# Charger.net
KiCad netlist of a schematic drawn in Altium Designer
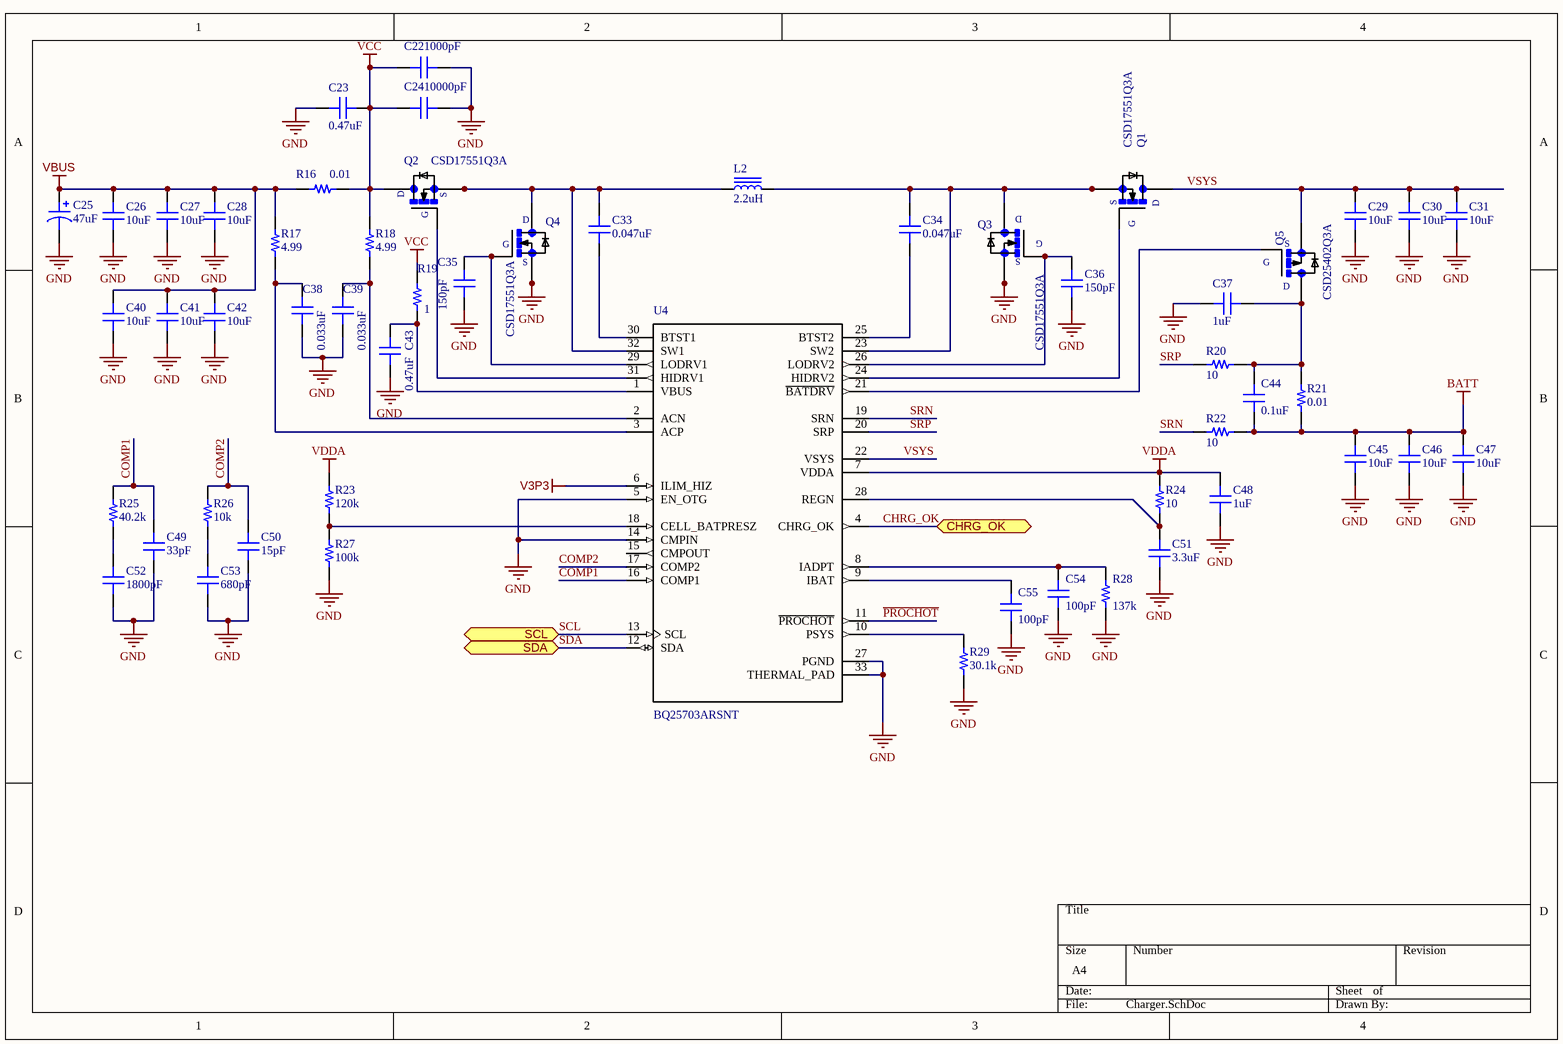
[diagram p0: Charger.SchDoc]

(export (version "E")
  (design (tool "Eeschema 10.0.6"))
  (components
    (comp (ref "C22")
      (value "1000pF")
      (footprint "CAP 0402/1005")
      (description "CAP CER 1000PF 50V X5R 0402")
      (fields
        (field (name "PART NUMBER") "GRM155R61H102KA01D")
        (field (name "MANUFACTURER") "Murata Electronics North America")
      )
      (libsource (lib "Celestial Library Database") (part "Capacitor"))
    )
    (comp (ref "C23")
      (value "0.47uF")
      (footprint "CAP 0603/1608")
      (description "CAP CER 0.47UF 50V X7R 0603")
      (fields
        (field (name "PART NUMBER") "C1608X7R1H474K080AC")
        (field (name "MANUFACTURER") "TDK Corporation")
      )
      (libsource (lib "Celestial Library Database") (part "Capacitor"))
    )
    (comp (ref "C24")
      (value "10000pF")
      (footprint "CAP 0402/1005")
      (description "CAP CER 10000PF 50V X7R 0402")
      (fields
        (field (name "PART NUMBER") "GCM155R71H103KA55D")
        (field (name "MANUFACTURER") "Murata Electronics North America")
      )
      (libsource (lib "Celestial Library Database") (part "Capacitor"))
    )
    (comp (ref "C25")
      (value "47uF")
      (footprint "CAP POL 2917/7343")
      (description "CAP TANT 47UF 35V 20% 2917")
      (fields (field (name "PART NUMBER") "T491X476M035AT") (field (name "MANUFACTURER") "Kemet"))
      (libsource (lib "Celestial Library Database") (part "Polarised Capacitor"))
    )
    (comp (ref "C26")
      (value "10uF")
      (footprint "CAP 0805/2012")
      (description "CAP CER 10UF 35V X5R 0805")
      (fields
        (field (name "PART NUMBER") "C2012X5R1V106M085AC")
        (field (name "MANUFACTURER") "TDK Corporation")
      )
      (libsource (lib "Celestial Library Database") (part "Capacitor"))
    )
    (comp (ref "C27")
      (value "10uF")
      (footprint "CAP 0805/2012")
      (description "CAP CER 10UF 35V X5R 0805")
      (fields
        (field (name "PART NUMBER") "C2012X5R1V106M085AC")
        (field (name "MANUFACTURER") "TDK Corporation")
      )
      (libsource (lib "Celestial Library Database") (part "Capacitor"))
    )
    (comp (ref "C28")
      (value "10uF")
      (footprint "CAP 0805/2012")
      (description "CAP CER 10UF 35V X5R 0805")
      (fields
        (field (name "PART NUMBER") "C2012X5R1V106M085AC")
        (field (name "MANUFACTURER") "TDK Corporation")
      )
      (libsource (lib "Celestial Library Database") (part "Capacitor"))
    )
    (comp (ref "C29")
      (value "10uF")
      (footprint "CAP 0805/2012")
      (description "CAP CER 10UF 35V X5R 0805")
      (fields
        (field (name "PART NUMBER") "C2012X5R1V106M085AC")
        (field (name "MANUFACTURER") "TDK Corporation")
      )
      (libsource (lib "Celestial Library Database") (part "Capacitor"))
    )
    (comp (ref "C30")
      (value "10uF")
      (footprint "CAP 0805/2012")
      (description "CAP CER 10UF 35V X5R 0805")
      (fields
        (field (name "PART NUMBER") "C2012X5R1V106M085AC")
        (field (name "MANUFACTURER") "TDK Corporation")
      )
      (libsource (lib "Celestial Library Database") (part "Capacitor"))
    )
    (comp (ref "C31")
      (value "10uF")
      (footprint "CAP 0805/2012")
      (description "CAP CER 10UF 35V X5R 0805")
      (fields
        (field (name "PART NUMBER") "C2012X5R1V106M085AC")
        (field (name "MANUFACTURER") "TDK Corporation")
      )
      (libsource (lib "Celestial Library Database") (part "Capacitor"))
    )
    (comp (ref "C33")
      (value "0.047uF")
      (footprint "CAP 0603/1608")
      (description "CAP CER 0.047UF 50V X7R 0603")
      (fields
        (field (name "PART NUMBER") "500R14W473KV4T")
        (field (name "MANUFACTURER") "Johanson Dielectrics Inc.")
      )
      (libsource (lib "Celestial Library Database") (part "Capacitor"))
    )
    (comp (ref "C34")
      (value "0.047uF")
      (footprint "CAP 0603/1608")
      (description "CAP CER 0.047UF 50V X7R 0603")
      (fields
        (field (name "PART NUMBER") "500R14W473KV4T")
        (field (name "MANUFACTURER") "Johanson Dielectrics Inc.")
      )
      (libsource (lib "Celestial Library Database") (part "Capacitor"))
    )
    (comp (ref "C35")
      (value "150pF")
      (footprint "CAP 0603/1608")
      (description "CAP CER 150PF 50V C0G 0603")
      (fields
        (field (name "PART NUMBER") "C1608C0G1H151K080AA")
        (field (name "MANUFACTURER") "TDK Corporation")
      )
      (libsource (lib "Celestial Library Database") (part "Capacitor"))
    )
    (comp (ref "C36")
      (value "150pF")
      (footprint "CAP 0603/1608")
      (description "CAP CER 150PF 50V C0G 0603")
      (fields
        (field (name "PART NUMBER") "C1608C0G1H151K080AA")
        (field (name "MANUFACTURER") "TDK Corporation")
      )
      (libsource (lib "Celestial Library Database") (part "Capacitor"))
    )
    (comp (ref "C37")
      (value "1uF")
      (footprint "CAP 0603/1608")
      (description "CAP CER 1UF 35V X7R 0603")
      (fields
        (field (name "PART NUMBER") "GRM188R7YA105KA12D")
        (field (name "MANUFACTURER") "Murata Electronics North America")
      )
      (libsource (lib "Celestial Library Database") (part "Capacitor"))
    )
    (comp (ref "C38")
      (value "0.033uF")
      (footprint "CAP 0603/1608")
      (description "CAP CER 0.033UF 50V X7R 0603")
      (fields
        (field (name "PART NUMBER") "C1608X7R1H333K080AA")
        (field (name "MANUFACTURER") "TDK Corporation")
      )
      (libsource (lib "Celestial Library Database") (part "Capacitor"))
    )
    (comp (ref "C39")
      (value "0.033uF")
      (footprint "CAP 0603/1608")
      (description "CAP CER 0.033UF 50V X7R 0603")
      (fields
        (field (name "PART NUMBER") "C1608X7R1H333K080AA")
        (field (name "MANUFACTURER") "TDK Corporation")
      )
      (libsource (lib "Celestial Library Database") (part "Capacitor"))
    )
    (comp (ref "C40")
      (value "10uF")
      (footprint "CAP 0805/2012")
      (description "CAP CER 10UF 35V X5R 0805")
      (fields
        (field (name "PART NUMBER") "C2012X5R1V106M085AC")
        (field (name "MANUFACTURER") "TDK Corporation")
      )
      (libsource (lib "Celestial Library Database") (part "Capacitor"))
    )
    (comp (ref "C41")
      (value "10uF")
      (footprint "CAP 0805/2012")
      (description "CAP CER 10UF 35V X5R 0805")
      (fields
        (field (name "PART NUMBER") "C2012X5R1V106M085AC")
        (field (name "MANUFACTURER") "TDK Corporation")
      )
      (libsource (lib "Celestial Library Database") (part "Capacitor"))
    )
    (comp (ref "C42")
      (value "10uF")
      (footprint "CAP 0805/2012")
      (description "CAP CER 10UF 35V X5R 0805")
      (fields
        (field (name "PART NUMBER") "C2012X5R1V106M085AC")
        (field (name "MANUFACTURER") "TDK Corporation")
      )
      (libsource (lib "Celestial Library Database") (part "Capacitor"))
    )
    (comp (ref "C43")
      (value "0.47uF")
      (footprint "CAP 0603/1608")
      (description "CAP CER 0.47UF 50V X5R 0603")
      (fields (field (name "PART NUMBER") "UMK107ABJ474KA-T") (field (name "MANUFACTURER") "Taiyo Yuden"))
      (libsource (lib "Celestial Library Database") (part "Capacitor"))
    )
    (comp (ref "C44")
      (value "0.1uF")
      (footprint "CAP 0603/1608")
      (description "CAP CER 0.1UF 25V X7R 0603")
      (fields
        (field (name "PART NUMBER") "C1608X7R1E104K080AA")
        (field (name "MANUFACTURER") "TDK Corporation")
      )
      (libsource (lib "Celestial Library Database") (part "Capacitor"))
    )
    (comp (ref "C45")
      (value "10uF")
      (footprint "CAP 0805/2012")
      (description "CAP CER 10UF 35V X5R 0805")
      (fields
        (field (name "PART NUMBER") "C2012X5R1V106M085AC")
        (field (name "MANUFACTURER") "TDK Corporation")
      )
      (libsource (lib "Celestial Library Database") (part "Capacitor"))
    )
    (comp (ref "C46")
      (value "10uF")
      (footprint "CAP 0805/2012")
      (description "CAP CER 10UF 35V X5R 0805")
      (fields
        (field (name "PART NUMBER") "C2012X5R1V106M085AC")
        (field (name "MANUFACTURER") "TDK Corporation")
      )
      (libsource (lib "Celestial Library Database") (part "Capacitor"))
    )
    (comp (ref "C47")
      (value "10uF")
      (footprint "CAP 0805/2012")
      (description "CAP CER 10UF 35V X5R 0805")
      (fields
        (field (name "PART NUMBER") "C2012X5R1V106M085AC")
        (field (name "MANUFACTURER") "TDK Corporation")
      )
      (libsource (lib "Celestial Library Database") (part "Capacitor"))
    )
    (comp (ref "C48")
      (value "1uF")
      (footprint "CAP 0603/1608")
      (description "CAP CER 1UF 35V X7R 0603")
      (fields
        (field (name "PART NUMBER") "GRM188R7YA105KA12D")
        (field (name "MANUFACTURER") "Murata Electronics North America")
      )
      (libsource (lib "Celestial Library Database") (part "Capacitor"))
    )
    (comp (ref "C49")
      (value "33pF")
      (footprint "CAP 0603/1608")
      (description "CAP CER 33PF 50V NPO 0603")
      (fields (field (name "PART NUMBER") "CC0603JRNPO9BN330") (field (name "MANUFACTURER") "Yageo"))
      (libsource (lib "Celestial Library Database") (part "Capacitor"))
    )
    (comp (ref "C50")
      (value "15pF")
      (footprint "CAP 0603/1608")
      (description "CAP CER 15PF 50V C0G/NP0 0603")
      (fields
        (field (name "PART NUMBER") "500R14N150JV4T")
        (field (name "MANUFACTURER") "Johanson Dielectrics Inc.")
      )
      (libsource (lib "Celestial Library Database") (part "Capacitor"))
    )
    (comp (ref "C51")
      (value "3.3uF")
      (footprint "CAP 0603/1608")
      (description "CAP CER 3.3UF 16V X5R 0603")
      (fields
        (field (name "PART NUMBER") "C1608X5R1C335K080AC")
        (field (name "MANUFACTURER") "TDK Corporation")
      )
      (libsource (lib "Celestial Library Database") (part "Capacitor"))
    )
    (comp (ref "C52")
      (value "1800pF")
      (footprint "CAP 0603/1608")
      (description "CAP CER 1800PF 50V X7R 0603")
      (fields
        (field (name "PART NUMBER") "CL10B182KB8NNNC")
        (field (name "MANUFACTURER") "Samsung Electro-Mechanics America, Inc.")
      )
      (libsource (lib "Celestial Library Database") (part "Capacitor"))
    )
    (comp (ref "C53")
      (value "680pF")
      (footprint "CAP 0603/1608")
      (description "CAP CER 680PF 50V X7R 0603")
      (fields
        (field (name "PART NUMBER") "CL10B681KB8NNNC")
        (field (name "MANUFACTURER") "Samsung Electro-Mechanics America, Inc.")
      )
      (libsource (lib "Celestial Library Database") (part "Capacitor"))
    )
    (comp (ref "C54")
      (value "100pF")
      (footprint "CAP 0603/1608")
      (description "CAP CER 100PF 50V NP0 0603")
      (fields
        (field (name "PART NUMBER") "CL10C101KB8NNNC")
        (field (name "MANUFACTURER") "Samsung Electro-Mechanics America, Inc.")
      )
      (libsource (lib "Celestial Library Database") (part "Capacitor"))
    )
    (comp (ref "C55")
      (value "100pF")
      (footprint "CAP 0603/1608")
      (description "CAP CER 100PF 50V NP0 0603")
      (fields
        (field (name "PART NUMBER") "CL10C101KB8NNNC")
        (field (name "MANUFACTURER") "Samsung Electro-Mechanics America, Inc.")
      )
      (libsource (lib "Celestial Library Database") (part "Capacitor"))
    )
    (comp (ref "L2")
      (value "2.2uH")
      (footprint "WURTH WE-HCI 7040")
      (description "FIXED IND 2.2UH 9A 11.4 MOHM SMD")
      (fields (field (name "PART NUMBER") "744311220") (field (name "MANUFACTURER") "Wurth Electronics Inc"))
      (libsource (lib "Celestial Library Database") (part "Inductor"))
    )
    (comp (ref "Q1")
      (value "CSD17551Q3A")
      (footprint "SON65P300X350X90-9N")
      (description "Trans MOSFET N-CH 30V 48A 8-Pin VSONP EP T/R")
      (fields (field (name "MF") "Texas Instruments"))
      (libsource (lib "CSD17551Q3A") (part "CSD17551Q3A"))
    )
    (comp (ref "Q2")
      (value "CSD17551Q3A")
      (footprint "SON65P300X350X90-9N")
      (description "Trans MOSFET N-CH 30V 48A 8-Pin VSONP EP T/R")
      (fields (field (name "MF") "Texas Instruments"))
      (libsource (lib "CSD17551Q3A") (part "CSD17551Q3A"))
    )
    (comp (ref "Q3")
      (value "CSD17551Q3A")
      (footprint "SON65P300X350X90-9N")
      (description "Trans MOSFET N-CH 30V 48A 8-Pin VSONP EP T/R")
      (fields (field (name "MF") "Texas Instruments"))
      (libsource (lib "CSD17551Q3A") (part "CSD17551Q3A"))
    )
    (comp (ref "Q4")
      (value "CSD17551Q3A")
      (footprint "SON65P300X350X90-9N")
      (description "Trans MOSFET N-CH 30V 48A 8-Pin VSONP EP T/R")
      (fields (field (name "MF") "Texas Instruments"))
      (libsource (lib "CSD17551Q3A") (part "CSD17551Q3A"))
    )
    (comp (ref "Q5")
      (value "CSD25402Q3A")
      (footprint "SON65P300X350X90-9N")
      (description "Trans MOSFET P-CH –20 V -15A NexFET™ Power MOSFET")
      (fields (field (name "MF") "Texas Instruments") (field (name "MP") "CSD17551Q3A"))
      (libsource (lib "CSD17551Q3A") (part "CSD25402Q3A"))
    )
    (comp (ref "R16")
      (value "0.01")
      (footprint "STACKPOLE CSR2512")
      (description "RES SMD 0.01 OHM 1% 1W 2512")
      (fields (field (name "PART NUMBER") "CSR25120R01F") (field (name "MANUFACTURER") "Riedon"))
      (libsource (lib "Celestial Library Database") (part "Resistor"))
    )
    (comp (ref "R17")
      (value "4.99")
      (footprint "RES 0603/1608")
      (description "RES SMD 4.99 OHM 1% 1/10W 0603")
      (fields (field (name "PART NUMBER") "RC0603FR-074R99L") (field (name "MANUFACTURER") "Yageo"))
      (libsource (lib "Celestial Library Database") (part "Resistor"))
    )
    (comp (ref "R18")
      (value "4.99")
      (footprint "RES 0603/1608")
      (description "RES SMD 4.99 OHM 1% 1/10W 0603")
      (fields (field (name "PART NUMBER") "RC0603FR-074R99L") (field (name "MANUFACTURER") "Yageo"))
      (libsource (lib "Celestial Library Database") (part "Resistor"))
    )
    (comp (ref "R19")
      (value "1")
      (footprint "RES 0603/1608")
      (description "RES SMD 1 OHM 5% 1/4W 0603")
      (fields (field (name "PART NUMBER") "RCS06031R00JNEA") (field (name "MANUFACTURER") "Vishay Dale"))
      (libsource (lib "Celestial Library Database") (part "Resistor"))
    )
    (comp (ref "R20")
      (value "10")
      (footprint "RES 0402/1005")
      (description "RES SMD 10 OHM 1% 1/10W 0402")
      (fields
        (field (name "PART NUMBER") "ERJ-2RKF10R0X")
        (field (name "MANUFACTURER") "Panasonic Electronic Components")
      )
      (libsource (lib "Celestial Library Database") (part "Resistor"))
    )
    (comp (ref "R21")
      (value "0.01")
      (footprint "STACKPOLE CSR2512")
      (description "RES SMD 0.01 OHM 1% 1W 2512")
      (fields (field (name "PART NUMBER") "CSR25120R01F") (field (name "MANUFACTURER") "Riedon"))
      (libsource (lib "Celestial Library Database") (part "Resistor"))
    )
    (comp (ref "R22")
      (value "10")
      (footprint "RES 0402/1005")
      (description "RES SMD 10 OHM 1% 1/10W 0402")
      (fields
        (field (name "PART NUMBER") "ERJ-2RKF10R0X")
        (field (name "MANUFACTURER") "Panasonic Electronic Components")
      )
      (libsource (lib "Celestial Library Database") (part "Resistor"))
    )
    (comp (ref "R23")
      (value "120k")
      (footprint "RES 0603/1608")
      (description "RES SMD 120K OHM 1% 1/10W 0603")
      (fields
        (field (name "PART NUMBER") "ERJ-3EKF1203V")
        (field (name "MANUFACTURER") "Panasonic Electronic Components")
      )
      (libsource (lib "Celestial Library Database") (part "Resistor"))
    )
    (comp (ref "R24")
      (value "10")
      (footprint "RES 0603/1608")
      (description "RES SMD 10 OHM 1% 1/10W 0603")
      (fields
        (field (name "PART NUMBER") "RMCF0603FT10R0")
        (field (name "MANUFACTURER") "Stackpole Electronics Inc.")
      )
      (libsource (lib "Celestial Library Database") (part "Resistor"))
    )
    (comp (ref "R25")
      (value "40.2k")
      (footprint "RES 0603/1608")
      (description "RES SMD 40.2K OHM 1% 1/10W 0603")
      (fields
        (field (name "PART NUMBER") "ERJ-3EKF4022V")
        (field (name "MANUFACTURER") "Panasonic Electronic Components")
      )
      (libsource (lib "Celestial Library Database") (part "Resistor"))
    )
    (comp (ref "R26")
      (value "10k")
      (footprint "RES 0603/1608")
      (description "RES SMD 10K OHM 1% 1/10W 0603")
      (fields
        (field (name "PART NUMBER") "ERJ-3EKF1002V")
        (field (name "MANUFACTURER") "Panasonic Electronic Components")
      )
      (libsource (lib "Celestial Library Database") (part "Resistor"))
    )
    (comp (ref "R27")
      (value "100k")
      (footprint "RES 0603/1608")
      (description "RES SMD 100K OHM 1% 1/10W 0603")
      (fields
        (field (name "PART NUMBER") "ERJ-3EKF1003V")
        (field (name "MANUFACTURER") "Panasonic Electronic Components")
      )
      (libsource (lib "Celestial Library Database") (part "Resistor"))
    )
    (comp (ref "R28")
      (value "137k")
      (footprint "RES 0603/1608")
      (description "RES SMD 137K OHM 1% 1/10W 0603")
      (fields
        (field (name "PART NUMBER") "ERJ-3EKF1373V")
        (field (name "MANUFACTURER") "Panasonic Electronic Components")
      )
      (libsource (lib "Celestial Library Database") (part "Resistor"))
    )
    (comp (ref "R29")
      (value "30.1k")
      (footprint "RES 0402/1005")
      (description "RES SMD 30.1K OHM 1% 1/10W 0402")
      (fields
        (field (name "PART NUMBER") "ERJ-2RKF3012X")
        (field (name "MANUFACTURER") "Panasonic Electronic Components")
      )
      (libsource (lib "Celestial Library Database") (part "Resistor"))
    )
    (comp (ref "U4")
      (value "BQ25703ARSNT")
      (footprint "QFN40P400X400X80-33N")
      (fields (field (name "MF") "Texas Instruments"))
      (libsource (lib "BQ25703ARSNT") (part "BQ25703ARSNT"))
    )
  )
  (nets
    (net (code "1") (name "/CHRG_OK") (class "Default")
      (node (ref "U4") (pin "4") (pinfunction "CHRG_OK_4") (pintype "output"))
    )
    (net (code "2") (name "/COMP1") (class "Default")
      (node (ref "C49") (pin "2") (pinfunction "2_2") (pintype "passive"))
      (node (ref "R25") (pin "2") (pinfunction "2_2") (pintype "passive"))
      (node (ref "U4") (pin "16") (pinfunction "COMP1_16") (pintype "input"))
    )
    (net (code "3") (name "/COMP2") (class "Default")
      (node (ref "C50") (pin "2") (pinfunction "2_2") (pintype "passive"))
      (node (ref "R26") (pin "2") (pinfunction "2_2") (pintype "passive"))
      (node (ref "U4") (pin "17") (pinfunction "COMP2_17") (pintype "input"))
    )
    (net (code "4") (name "/SCL") (class "Default")
      (node (ref "U4") (pin "13") (pinfunction "SCL_13") (pintype "input"))
    )
    (net (code "5") (name "/SDA") (class "Default")
      (node (ref "U4") (pin "12") (pinfunction "SDA_12") (pintype "bidirectional"))
    )
    (net (code "6") (name "/SRN") (class "Default")
      (node (ref "R22") (pin "1") (pinfunction "1_1") (pintype "passive"))
      (node (ref "U4") (pin "19") (pinfunction "SRN_19") (pintype "power_in"))
    )
    (net (code "7") (name "/SRP") (class "Default")
      (node (ref "R20") (pin "1") (pinfunction "1_1") (pintype "passive"))
      (node (ref "U4") (pin "20") (pinfunction "SRP_20") (pintype "power_in"))
    )
    (net (code "8") (name "/VSYS") (class "Default")
      (node (ref "C29") (pin "2") (pinfunction "2_2") (pintype "passive"))
      (node (ref "C30") (pin "2") (pinfunction "2_2") (pintype "passive"))
      (node (ref "C31") (pin "2") (pinfunction "2_2") (pintype "passive"))
      (node (ref "Q1") (pin "5") (pinfunction "D_5") (pintype "passive"))
      (node (ref "Q5") (pin "5") (pinfunction "D_5") (pintype "passive"))
      (node (ref "U4") (pin "22") (pinfunction "VSYS_22") (pintype "power_in"))
    )
    (net (code "9") (name "/~{PROCHOT}") (class "Default")
      (node (ref "U4") (pin "11") (pinfunction "~{PROCHOT}_11") (pintype "output"))
    )
    (net (code "10") (name "BATT") (class "Default")
      (node (ref "C44") (pin "1") (pinfunction "1_1") (pintype "passive"))
      (node (ref "C45") (pin "1") (pinfunction "1_1") (pintype "passive"))
      (node (ref "C46") (pin "2") (pinfunction "2_2") (pintype "passive"))
      (node (ref "C47") (pin "2") (pinfunction "2_2") (pintype "passive"))
      (node (ref "R21") (pin "1") (pinfunction "1_1") (pintype "passive"))
      (node (ref "R22") (pin "2") (pinfunction "2_2") (pintype "passive"))
    )
    (net (code "11") (name "GND") (class "Default")
      (node (ref "C22") (pin "2") (pinfunction "2_2") (pintype "passive"))
      (node (ref "C23") (pin "2") (pinfunction "2_2") (pintype "passive"))
      (node (ref "C24") (pin "2") (pinfunction "2_2") (pintype "passive"))
      (node (ref "C25") (pin "2") (pinfunction "2_2") (pintype "passive"))
      (node (ref "C26") (pin "1") (pinfunction "1_1") (pintype "passive"))
      (node (ref "C27") (pin "1") (pinfunction "1_1") (pintype "passive"))
      (node (ref "C28") (pin "1") (pinfunction "1_1") (pintype "passive"))
      (node (ref "C29") (pin "1") (pinfunction "1_1") (pintype "passive"))
      (node (ref "C30") (pin "1") (pinfunction "1_1") (pintype "passive"))
      (node (ref "C31") (pin "1") (pinfunction "1_1") (pintype "passive"))
      (node (ref "C35") (pin "1") (pinfunction "1_1") (pintype "passive"))
      (node (ref "C36") (pin "1") (pinfunction "1_1") (pintype "passive"))
      (node (ref "C37") (pin "1") (pinfunction "1_1") (pintype "passive"))
      (node (ref "C38") (pin "1") (pinfunction "1_1") (pintype "passive"))
      (node (ref "C39") (pin "1") (pinfunction "1_1") (pintype "passive"))
      (node (ref "C40") (pin "1") (pinfunction "1_1") (pintype "passive"))
      (node (ref "C41") (pin "1") (pinfunction "1_1") (pintype "passive"))
      (node (ref "C42") (pin "1") (pinfunction "1_1") (pintype "passive"))
      (node (ref "C43") (pin "2") (pinfunction "2_2") (pintype "passive"))
      (node (ref "C45") (pin "2") (pinfunction "2_2") (pintype "passive"))
      (node (ref "C46") (pin "1") (pinfunction "1_1") (pintype "passive"))
      (node (ref "C47") (pin "1") (pinfunction "1_1") (pintype "passive"))
      (node (ref "C48") (pin "2") (pinfunction "2_2") (pintype "passive"))
      (node (ref "C49") (pin "1") (pinfunction "1_1") (pintype "passive"))
      (node (ref "C50") (pin "1") (pinfunction "1_1") (pintype "passive"))
      (node (ref "C51") (pin "1") (pinfunction "1_1") (pintype "passive"))
      (node (ref "C52") (pin "1") (pinfunction "1_1") (pintype "passive"))
      (node (ref "C53") (pin "1") (pinfunction "1_1") (pintype "passive"))
      (node (ref "C54") (pin "1") (pinfunction "1_1") (pintype "passive"))
      (node (ref "C55") (pin "1") (pinfunction "1_1") (pintype "passive"))
      (node (ref "Q3") (pin "1") (pinfunction "S_1") (pintype "passive"))
      (node (ref "Q3") (pin "2") (pinfunction "S_2") (pintype "passive"))
      (node (ref "Q3") (pin "3") (pinfunction "S_3") (pintype "passive"))
      (node (ref "Q4") (pin "1") (pinfunction "S_1") (pintype "passive"))
      (node (ref "Q4") (pin "2") (pinfunction "S_2") (pintype "passive"))
      (node (ref "Q4") (pin "3") (pinfunction "S_3") (pintype "passive"))
      (node (ref "R27") (pin "1") (pinfunction "1_1") (pintype "passive"))
      (node (ref "R28") (pin "1") (pinfunction "1_1") (pintype "passive"))
      (node (ref "R29") (pin "1") (pinfunction "1_1") (pintype "passive"))
      (node (ref "U4") (pin "14") (pinfunction "CMPIN_14") (pintype "input"))
      (node (ref "U4") (pin "27") (pinfunction "PGND_27") (pintype "power_in"))
      (node (ref "U4") (pin "33") (pinfunction "THERMAL_PAD_33") (pintype "power_in"))
      (node (ref "U4") (pin "5") (pinfunction "EN_OTG_5") (pintype "input"))
    )
    (net (code "12") (name "Net-(C37-Pad2)") (class "Default")
      (node (ref "C37") (pin "2") (pinfunction "2_2") (pintype "passive"))
      (node (ref "C44") (pin "2") (pinfunction "2_2") (pintype "passive"))
      (node (ref "Q5") (pin "1") (pinfunction "S_1") (pintype "passive"))
      (node (ref "Q5") (pin "2") (pinfunction "S_2") (pintype "passive"))
      (node (ref "Q5") (pin "3") (pinfunction "S_3") (pintype "passive"))
      (node (ref "R20") (pin "2") (pinfunction "2_2") (pintype "passive"))
      (node (ref "R21") (pin "2") (pinfunction "2_2") (pintype "passive"))
    )
    (net (code "13") (name "Net-(C52-Pad2)") (class "Default")
      (node (ref "C52") (pin "2") (pinfunction "2_2") (pintype "passive"))
      (node (ref "R25") (pin "1") (pinfunction "1_1") (pintype "passive"))
    )
    (net (code "14") (name "Net-(C53-Pad2)") (class "Default")
      (node (ref "C53") (pin "2") (pinfunction "2_2") (pintype "passive"))
      (node (ref "R26") (pin "1") (pinfunction "1_1") (pintype "passive"))
    )
    (net (code "15") (name "Net-(Q1-G)") (class "Default")
      (node (ref "Q1") (pin "4") (pinfunction "G_4") (pintype "passive"))
      (node (ref "U4") (pin "24") (pinfunction "HIDRV2_24") (pintype "output"))
    )
    (net (code "16") (name "Net-(Q2-G)") (class "Default")
      (node (ref "Q2") (pin "4") (pinfunction "G_4") (pintype "passive"))
      (node (ref "U4") (pin "31") (pinfunction "HIDRV1_31") (pintype "output"))
    )
    (net (code "17") (name "Net-(Q3-D)") (class "Default")
      (node (ref "C34") (pin "2") (pinfunction "2_2") (pintype "passive"))
      (node (ref "L2") (pin "2") (pinfunction "2_2") (pintype "passive"))
      (node (ref "Q1") (pin "1") (pinfunction "S_1") (pintype "passive"))
      (node (ref "Q1") (pin "2") (pinfunction "S_2") (pintype "passive"))
      (node (ref "Q1") (pin "3") (pinfunction "S_3") (pintype "passive"))
      (node (ref "Q3") (pin "5") (pinfunction "D_5") (pintype "passive"))
      (node (ref "U4") (pin "23") (pinfunction "SW2_23") (pintype "power_in"))
    )
    (net (code "18") (name "Net-(Q3-G)") (class "Default")
      (node (ref "C36") (pin "2") (pinfunction "2_2") (pintype "passive"))
      (node (ref "Q3") (pin "4") (pinfunction "G_4") (pintype "passive"))
      (node (ref "U4") (pin "26") (pinfunction "LODRV2_26") (pintype "output"))
    )
    (net (code "19") (name "Net-(Q4-D)") (class "Default")
      (node (ref "C33") (pin "2") (pinfunction "2_2") (pintype "passive"))
      (node (ref "L2") (pin "1") (pinfunction "1_1") (pintype "passive"))
      (node (ref "Q2") (pin "1") (pinfunction "S_1") (pintype "passive"))
      (node (ref "Q2") (pin "2") (pinfunction "S_2") (pintype "passive"))
      (node (ref "Q2") (pin "3") (pinfunction "S_3") (pintype "passive"))
      (node (ref "Q4") (pin "5") (pinfunction "D_5") (pintype "passive"))
      (node (ref "U4") (pin "32") (pinfunction "SW1_32") (pintype "power_in"))
    )
    (net (code "20") (name "Net-(Q4-G)") (class "Default")
      (node (ref "C35") (pin "2") (pinfunction "2_2") (pintype "passive"))
      (node (ref "Q4") (pin "4") (pinfunction "G_4") (pintype "passive"))
      (node (ref "U4") (pin "29") (pinfunction "LODRV1_29") (pintype "output"))
    )
    (net (code "21") (name "Net-(Q5-G)") (class "Default")
      (node (ref "Q5") (pin "4") (pinfunction "G_4") (pintype "passive"))
      (node (ref "U4") (pin "21") (pinfunction "~{BATDRV}_21") (pintype "output"))
    )
    (net (code "22") (name "Net-(U4-ACN)") (class "Default")
      (node (ref "C39") (pin "2") (pinfunction "2_2") (pintype "passive"))
      (node (ref "R18") (pin "1") (pinfunction "1_1") (pintype "passive"))
      (node (ref "U4") (pin "2") (pinfunction "ACN_2") (pintype "power_in"))
    )
    (net (code "23") (name "Net-(U4-ACP)") (class "Default")
      (node (ref "C38") (pin "2") (pinfunction "2_2") (pintype "passive"))
      (node (ref "R17") (pin "1") (pinfunction "1_1") (pintype "passive"))
      (node (ref "U4") (pin "3") (pinfunction "ACP_3") (pintype "power_in"))
    )
    (net (code "24") (name "Net-(U4-BTST1)") (class "Default")
      (node (ref "C33") (pin "1") (pinfunction "1_1") (pintype "passive"))
      (node (ref "U4") (pin "30") (pinfunction "BTST1_30") (pintype "power_in"))
    )
    (net (code "25") (name "Net-(U4-BTST2)") (class "Default")
      (node (ref "C34") (pin "1") (pinfunction "1_1") (pintype "passive"))
      (node (ref "U4") (pin "25") (pinfunction "BTST2_25") (pintype "power_in"))
    )
    (net (code "26") (name "Net-(U4-CELL_BATPRESZ)") (class "Default")
      (node (ref "R23") (pin "1") (pinfunction "1_1") (pintype "passive"))
      (node (ref "R27") (pin "2") (pinfunction "2_2") (pintype "passive"))
      (node (ref "U4") (pin "18") (pinfunction "CELL_BATPRESZ_18") (pintype "input"))
    )
    (net (code "27") (name "Net-(U4-IADPT)") (class "Default")
      (node (ref "C54") (pin "2") (pinfunction "2_2") (pintype "passive"))
      (node (ref "R28") (pin "2") (pinfunction "2_2") (pintype "passive"))
      (node (ref "U4") (pin "8") (pinfunction "IADPT_8") (pintype "output"))
    )
    (net (code "28") (name "Net-(U4-IBAT)") (class "Default")
      (node (ref "C55") (pin "2") (pinfunction "2_2") (pintype "passive"))
      (node (ref "U4") (pin "9") (pinfunction "IBAT_9") (pintype "output"))
    )
    (net (code "29") (name "Net-(U4-PSYS)") (class "Default")
      (node (ref "R29") (pin "2") (pinfunction "2_2") (pintype "passive"))
      (node (ref "U4") (pin "10") (pinfunction "PSYS_10") (pintype "output"))
    )
    (net (code "30") (name "Net-(U4-REGN)") (class "Default")
      (node (ref "C51") (pin "2") (pinfunction "2_2") (pintype "passive"))
      (node (ref "R24") (pin "1") (pinfunction "1_1") (pintype "passive"))
      (node (ref "U4") (pin "28") (pinfunction "REGN_28") (pintype "power_in"))
    )
    (net (code "31") (name "Net-(U4-VBUS)") (class "Default")
      (node (ref "C43") (pin "1") (pinfunction "1_1") (pintype "passive"))
      (node (ref "R19") (pin "2") (pinfunction "2_2") (pintype "passive"))
      (node (ref "U4") (pin "1") (pinfunction "VBUS_1") (pintype "power_in"))
    )
    (net (code "32") (name "V3P3") (class "Default")
      (node (ref "U4") (pin "6") (pinfunction "ILIM_HIZ_6") (pintype "input"))
    )
    (net (code "33") (name "VBUS") (class "Default")
      (node (ref "C25") (pin "1") (pinfunction "1_1") (pintype "passive"))
      (node (ref "C26") (pin "2") (pinfunction "2_2") (pintype "passive"))
      (node (ref "C27") (pin "2") (pinfunction "2_2") (pintype "passive"))
      (node (ref "C28") (pin "2") (pinfunction "2_2") (pintype "passive"))
      (node (ref "C40") (pin "2") (pinfunction "2_2") (pintype "passive"))
      (node (ref "C41") (pin "2") (pinfunction "2_2") (pintype "passive"))
      (node (ref "C42") (pin "2") (pinfunction "2_2") (pintype "passive"))
      (node (ref "R16") (pin "1") (pinfunction "1_1") (pintype "passive"))
      (node (ref "R17") (pin "2") (pinfunction "2_2") (pintype "passive"))
    )
    (net (code "34") (name "VCC") (class "Default")
      (node (ref "C22") (pin "1") (pinfunction "1_1") (pintype "passive"))
      (node (ref "C23") (pin "1") (pinfunction "1_1") (pintype "passive"))
      (node (ref "C24") (pin "1") (pinfunction "1_1") (pintype "passive"))
      (node (ref "Q2") (pin "5") (pinfunction "D_5") (pintype "passive"))
      (node (ref "R16") (pin "2") (pinfunction "2_2") (pintype "passive"))
      (node (ref "R18") (pin "2") (pinfunction "2_2") (pintype "passive"))
      (node (ref "R19") (pin "1") (pinfunction "1_1") (pintype "passive"))
    )
    (net (code "35") (name "VDDA") (class "Default")
      (node (ref "C48") (pin "1") (pinfunction "1_1") (pintype "passive"))
      (node (ref "R23") (pin "2") (pinfunction "2_2") (pintype "passive"))
      (node (ref "R24") (pin "2") (pinfunction "2_2") (pintype "passive"))
      (node (ref "U4") (pin "7") (pinfunction "VDDA_7") (pintype "power_in"))
    )
    (net (code "36") (name "unconnected-(U4-CMPOUT-Pad15)") (class "Default")
      (node (ref "U4") (pin "15") (pinfunction "CMPOUT_15") (pintype "output"))
    )
  )
)
